# dimmerPower4.net
KiCad netlist of a schematic drawn in EAGLE
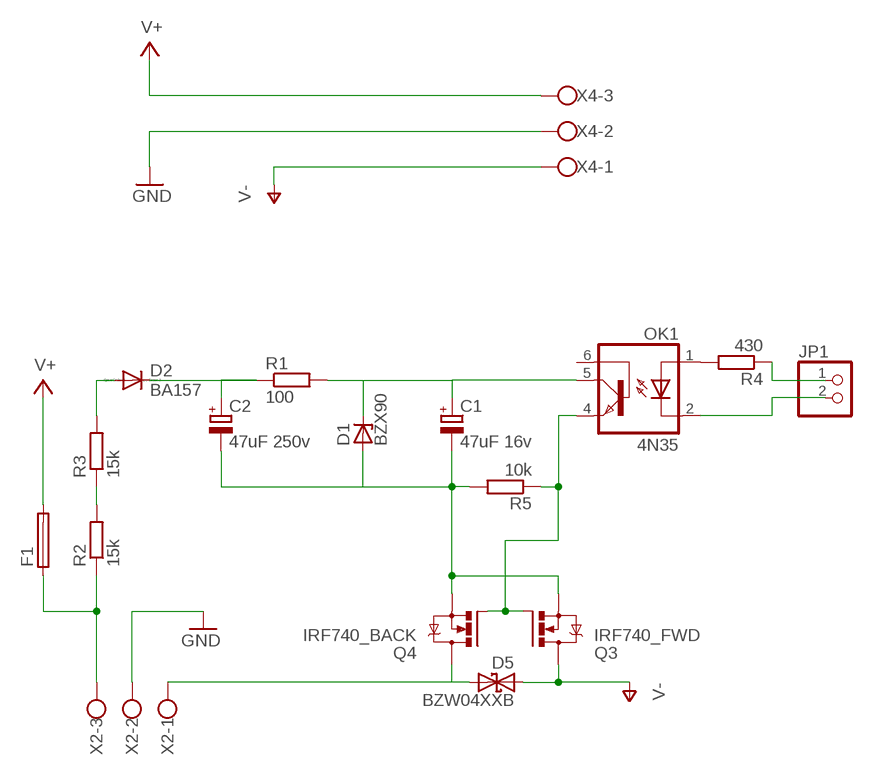
[diagram p0: schematic, sheet 1]

(export (version "E")
  (design (tool "Eeschema 10.0.6"))
  (components
    (comp (ref "C1")
      (value "47uF 16v")
      (footprint "eagle-import:E2,5-6")
      (libsource (lib "eagle-import") (part "CPOL-EUE2.5-6"))
    )
    (comp (ref "C2")
      (value "47uF 250v")
      (footprint "eagle-import:E5-13")
      (libsource (lib "eagle-import") (part "CPOL-EUE5-13"))
    )
    (comp (ref "D1")
      (value "BZX90")
      (footprint "eagle-import:DO34Z7")
      (libsource (lib "eagle-import") (part "BZX90"))
    )
    (comp (ref "D2")
      (value "BA157")
      (footprint "eagle-import:P1-10")
      (libsource (lib "eagle-import") (part "BA157"))
    )
    (comp (ref "D5")
      (value "BZW04XXB")
      (footprint "eagle-import:F126Z12")
      (libsource (lib "eagle-import") (part "BZW04XXB"))
    )
    (comp (ref "F1")
      (value "SH22,5")
      (footprint "eagle-import:SH22,5")
      (fields (field (name "MF") "SCHURTER") (field (name "MPN") "0031.8201"))
      (libsource (lib "eagle-import") (part "SH22,5"))
    )
    (comp (ref "JP1")
      (value "PINHD-1X2")
      (footprint "eagle-import:1X02")
      (libsource (lib "eagle-import") (part "PINHD-1X2"))
    )
    (comp (ref "OK1")
      (value "4N35")
      (footprint "eagle-import:DIL06")
      (fields (field (name "MF") "FAIRCHILD SEMICONDUCTOR"))
      (libsource (lib "eagle-import") (part "4N35"))
    )
    (comp (ref "Q3")
      (value "IRF740_FWD")
      (footprint "eagle-import:TO220BV_FWD")
      (libsource (lib "eagle-import") (part "IRF740_FWD"))
    )
    (comp (ref "Q4")
      (value "IRF740_BACK")
      (footprint "eagle-import:TO220BV_BACK")
      (libsource (lib "eagle-import") (part "IRF740_BACK"))
    )
    (comp (ref "R1")
      (value "100")
      (footprint "eagle-import:0204_7")
      (libsource (lib "eagle-import") (part "R-EU_0204/7"))
    )
    (comp (ref "R2")
      (value "15k")
      (footprint "eagle-import:P0613_15")
      (libsource (lib "eagle-import") (part "R-EU_0613/15"))
    )
    (comp (ref "R3")
      (value "15k")
      (footprint "eagle-import:P0613_15")
      (libsource (lib "eagle-import") (part "R-EU_0613/15"))
    )
    (comp (ref "R4")
      (value "430")
      (footprint "eagle-import:0204_7")
      (libsource (lib "eagle-import") (part "R-EU_0204/7"))
    )
    (comp (ref "R5")
      (value "10k")
      (footprint "eagle-import:0204_7")
      (libsource (lib "eagle-import") (part "R-EU_0204/7"))
    )
    (comp (ref "X2")
      (value "W237-103")
      (footprint "eagle-import:W237-103")
      (fields (field (name "MPN") "237-103"))
      (libsource (lib "eagle-import") (part "W237-103"))
    )
    (comp (ref "X4")
      (value "W237-103")
      (footprint "eagle-import:W237-103")
      (fields (field (name "MPN") "237-103"))
      (libsource (lib "eagle-import") (part "W237-103"))
    )
  )
  (nets
    (net (code "1") (name "GND") (class "Default")
      (node (ref "X2") (pin "2") (pinfunction "KL_2") (pintype "passive"))
      (node (ref "X4") (pin "2") (pinfunction "KL_2") (pintype "passive"))
    )
    (net (code "2") (name "Net-(C1-Pad-)") (class "Default")
      (node (ref "C1") (pin "-") (pinfunction "-_-") (pintype "passive"))
      (node (ref "C2") (pin "-") (pinfunction "-_-") (pintype "passive"))
      (node (ref "D1") (pin "A") (pinfunction "A_A") (pintype "passive"))
      (node (ref "Q3") (pin "S") (pinfunction "S_S") (pintype "passive"))
      (node (ref "Q4") (pin "S") (pinfunction "S_S") (pintype "passive"))
      (node (ref "R5") (pin "2") (pinfunction "2_2") (pintype "passive"))
    )
    (net (code "3") (name "Net-(C2-Pad+)") (class "Default")
      (node (ref "C2") (pin "+") (pinfunction "+_+") (pintype "passive"))
      (node (ref "D2") (pin "C") (pinfunction "C_C") (pintype "passive"))
      (node (ref "R1") (pin "1") (pinfunction "1_1") (pintype "passive"))
    )
    (net (code "4") (name "Net-(D2-PadA)") (class "Default")
      (node (ref "D2") (pin "A") (pinfunction "A_A") (pintype "passive"))
      (node (ref "R3") (pin "2") (pinfunction "2_2") (pintype "passive"))
    )
    (net (code "5") (name "Net-(D5-2)") (class "Default")
      (node (ref "D5") (pin "C") (pinfunction "2_C") (pintype "passive"))
      (node (ref "Q4") (pin "D") (pinfunction "D_D") (pintype "passive"))
      (node (ref "X2") (pin "1") (pinfunction "KL_1") (pintype "passive"))
    )
    (net (code "6") (name "Net-(JP1-Pad1)") (class "Default")
      (node (ref "JP1") (pin "1") (pinfunction "1_1") (pintype "passive"))
      (node (ref "R4") (pin "1") (pinfunction "1_1") (pintype "passive"))
    )
    (net (code "7") (name "Net-(OK1-A)") (class "Default")
      (node (ref "OK1") (pin "1") (pinfunction "A_1") (pintype "passive"))
      (node (ref "R4") (pin "2") (pinfunction "2_2") (pintype "passive"))
    )
    (net (code "8") (name "Net-(OK1-C)") (class "Default")
      (node (ref "JP1") (pin "2") (pinfunction "2_2") (pintype "passive"))
      (node (ref "OK1") (pin "2") (pinfunction "C_2") (pintype "passive"))
    )
    (net (code "9") (name "Net-(OK1-COL)") (class "Default")
      (node (ref "C1") (pin "+") (pinfunction "+_+") (pintype "passive"))
      (node (ref "D1") (pin "C") (pinfunction "C_C") (pintype "passive"))
      (node (ref "OK1") (pin "5") (pinfunction "COL_5") (pintype "passive"))
      (node (ref "R1") (pin "2") (pinfunction "2_2") (pintype "passive"))
    )
    (net (code "10") (name "Net-(OK1-EMI)") (class "Default")
      (node (ref "OK1") (pin "4") (pinfunction "EMI_4") (pintype "passive"))
      (node (ref "Q3") (pin "G") (pinfunction "G_G") (pintype "passive"))
      (node (ref "Q4") (pin "G") (pinfunction "G_G") (pintype "passive"))
      (node (ref "R5") (pin "1") (pinfunction "1_1") (pintype "passive"))
    )
    (net (code "11") (name "Net-(R2-Pad2)") (class "Default")
      (node (ref "R2") (pin "2") (pinfunction "2_2") (pintype "passive"))
      (node (ref "R3") (pin "1") (pinfunction "1_1") (pintype "passive"))
    )
    (net (code "12") (name "Net-(X2C-KL)") (class "Default")
      (node (ref "F1") (pin "1") (pinfunction "1_1") (pintype "passive"))
      (node (ref "R2") (pin "1") (pinfunction "1_1") (pintype "passive"))
      (node (ref "X2") (pin "3") (pinfunction "KL_3") (pintype "passive"))
    )
    (net (code "13") (name "V+") (class "Default")
      (node (ref "F1") (pin "2") (pinfunction "2_2") (pintype "passive"))
      (node (ref "X4") (pin "3") (pinfunction "KL_3") (pintype "passive"))
    )
    (net (code "14") (name "V-") (class "Default")
      (node (ref "D5") (pin "A") (pinfunction "1_A") (pintype "passive"))
      (node (ref "Q3") (pin "D") (pinfunction "D_D") (pintype "passive"))
      (node (ref "X4") (pin "1") (pinfunction "KL_1") (pintype "passive"))
    )
    (net (code "15") (name "unconnected-(OK1-BAS-Pad6)") (class "Default")
      (node (ref "OK1") (pin "6") (pinfunction "BAS_6") (pintype "passive"))
    )
  )
)
